# CombinedBoard_revA_1.net
KiCad netlist of a schematic drawn in EAGLE
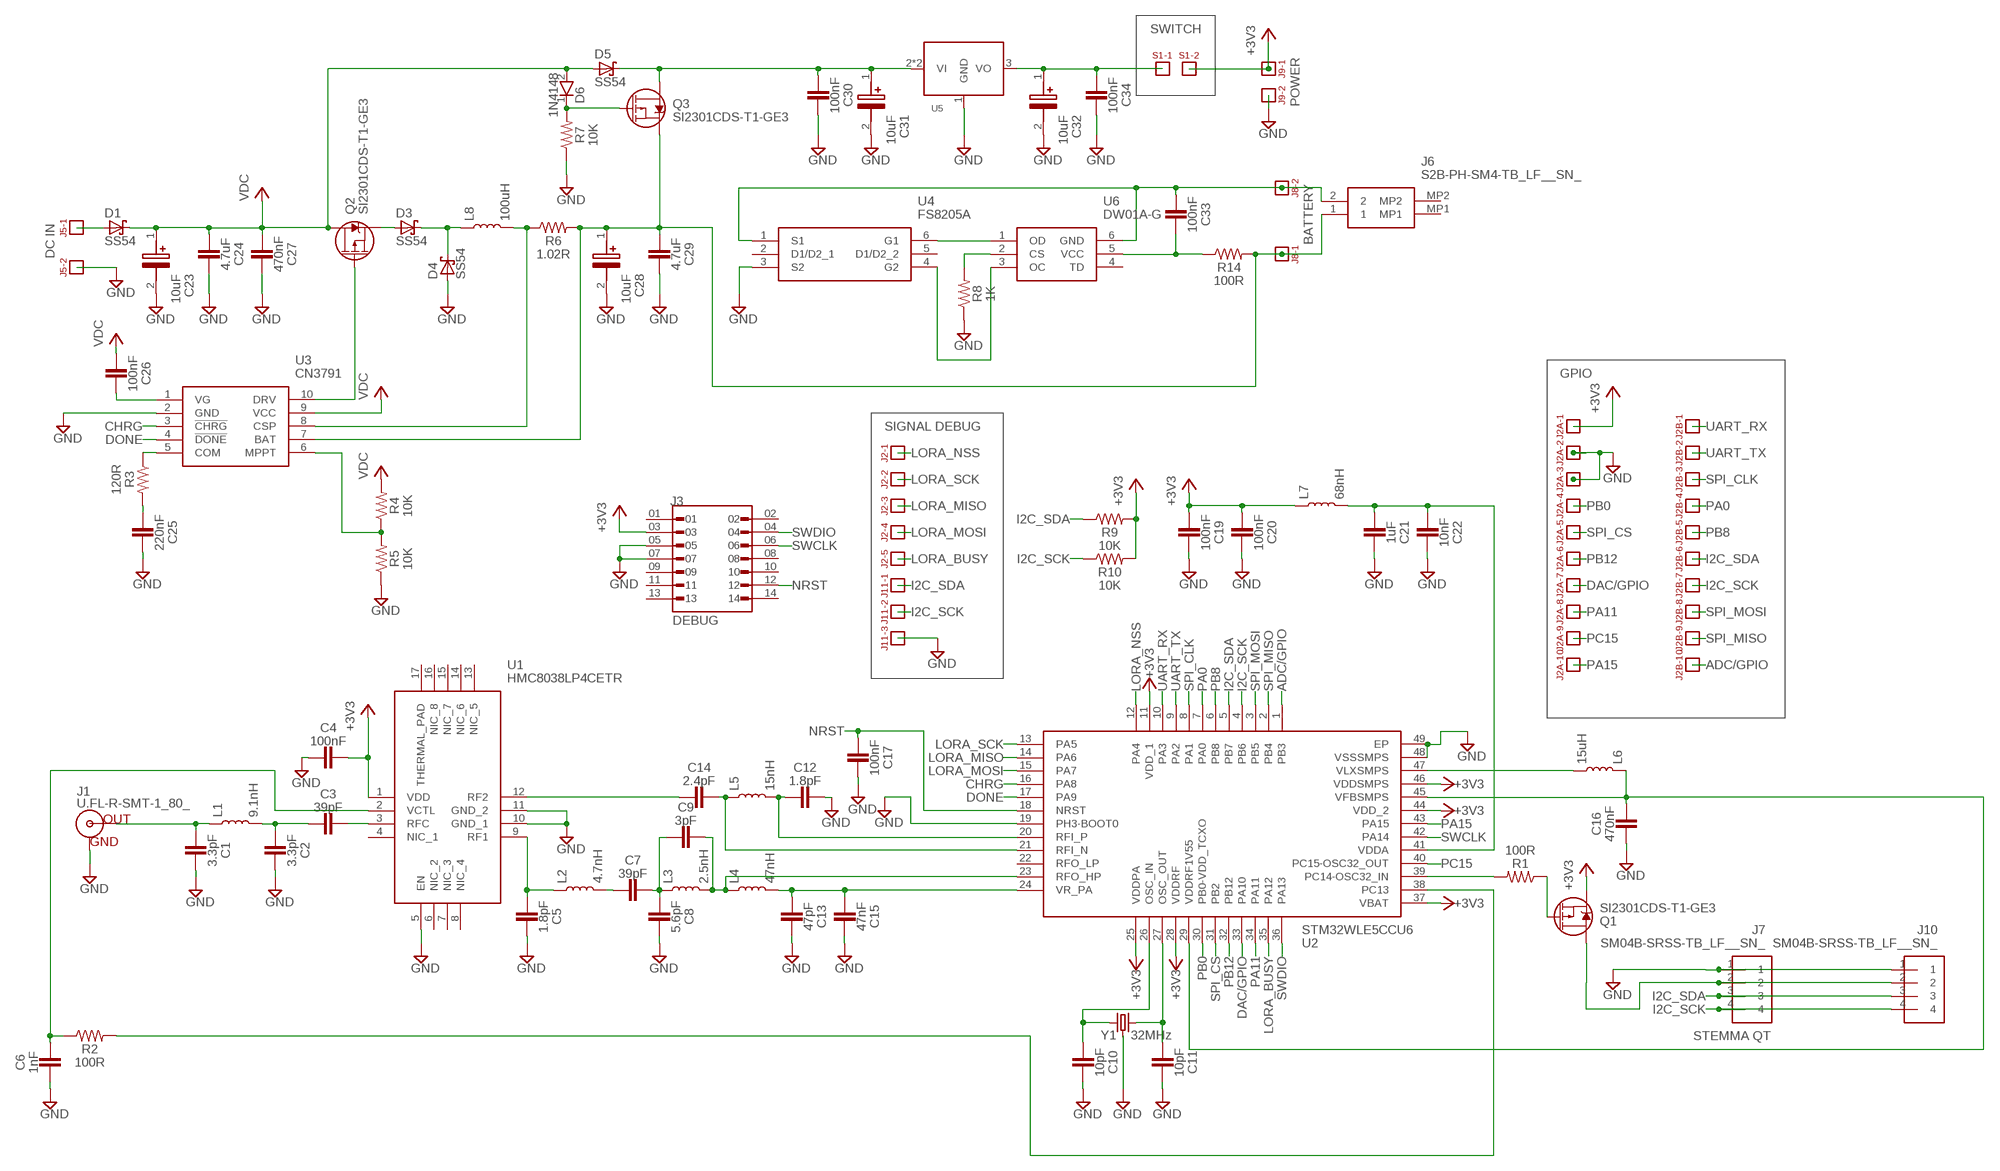
[diagram p0: schematic, sheet 1]

(export (version "E")
  (design (tool "Eeschema 10.0.6"))
  (components
    (comp (ref "C1")
      (value "3.3pF")
      (footprint "eagle-import:0402")
      (libsource (lib "eagle-import") (part "C_0402"))
    )
    (comp (ref "C2")
      (value "3.3pF")
      (footprint "eagle-import:0402")
      (libsource (lib "eagle-import") (part "C_0402"))
    )
    (comp (ref "C3")
      (value "39pF")
      (footprint "eagle-import:0402")
      (libsource (lib "eagle-import") (part "C_0402"))
    )
    (comp (ref "C4")
      (value "100nF")
      (footprint "eagle-import:0402")
      (libsource (lib "eagle-import") (part "C_0402"))
    )
    (comp (ref "C5")
      (value "1.8pF")
      (footprint "eagle-import:0402")
      (libsource (lib "eagle-import") (part "C_0402"))
    )
    (comp (ref "C6")
      (value "1nF")
      (footprint "eagle-import:0603")
      (libsource (lib "eagle-import") (part "C_0603"))
    )
    (comp (ref "C7")
      (value "39pF")
      (footprint "eagle-import:0402")
      (libsource (lib "eagle-import") (part "C_0402"))
    )
    (comp (ref "C8")
      (value "5.6pF")
      (footprint "eagle-import:0402")
      (libsource (lib "eagle-import") (part "C_0402"))
    )
    (comp (ref "C9")
      (value "3pF")
      (footprint "eagle-import:0603")
      (libsource (lib "eagle-import") (part "C_0603"))
    )
    (comp (ref "C10")
      (value "10pF")
      (footprint "eagle-import:0402")
      (libsource (lib "eagle-import") (part "C_0402"))
    )
    (comp (ref "C11")
      (value "10pF")
      (footprint "eagle-import:0402")
      (libsource (lib "eagle-import") (part "C_0402"))
    )
    (comp (ref "C12")
      (value "1.8pF")
      (footprint "eagle-import:0402")
      (libsource (lib "eagle-import") (part "C_0402"))
    )
    (comp (ref "C13")
      (value "47pF")
      (footprint "eagle-import:0603")
      (libsource (lib "eagle-import") (part "C_0603"))
    )
    (comp (ref "C14")
      (value "2.4pF")
      (footprint "eagle-import:0402")
      (libsource (lib "eagle-import") (part "C_0402"))
    )
    (comp (ref "C15")
      (value "47nF")
      (footprint "eagle-import:0603")
      (libsource (lib "eagle-import") (part "C_0603"))
    )
    (comp (ref "C16")
      (value "470nF")
      (footprint "eagle-import:0402")
      (libsource (lib "eagle-import") (part "C_0402"))
    )
    (comp (ref "C17")
      (value "100nF")
      (footprint "eagle-import:0402")
      (libsource (lib "eagle-import") (part "C_0402"))
    )
    (comp (ref "C19")
      (value "100nF")
      (footprint "eagle-import:0402")
      (libsource (lib "eagle-import") (part "C_0402"))
    )
    (comp (ref "C20")
      (value "100nF")
      (footprint "eagle-import:0402")
      (libsource (lib "eagle-import") (part "C_0402"))
    )
    (comp (ref "C21")
      (value "1uF")
      (footprint "eagle-import:0402")
      (libsource (lib "eagle-import") (part "C_0402"))
    )
    (comp (ref "C22")
      (value "10nF")
      (footprint "eagle-import:0402")
      (libsource (lib "eagle-import") (part "C_0402"))
    )
    (comp (ref "C23")
      (value "10uF")
      (footprint "eagle-import:4MM_SMD_ECAP")
      (libsource (lib "eagle-import") (part "4MM_SMD_ECAP"))
    )
    (comp (ref "C24")
      (value "4.7uF")
      (footprint "eagle-import:1206")
      (libsource (lib "eagle-import") (part "C_1206"))
    )
    (comp (ref "C25")
      (value "220nF")
      (footprint "eagle-import:0603")
      (libsource (lib "eagle-import") (part "C_0603"))
    )
    (comp (ref "C26")
      (value "100nF")
      (footprint "eagle-import:0402")
      (libsource (lib "eagle-import") (part "C_0402"))
    )
    (comp (ref "C27")
      (value "470nF")
      (footprint "eagle-import:0805")
      (libsource (lib "eagle-import") (part "C_0805"))
    )
    (comp (ref "C28")
      (value "10uF")
      (footprint "eagle-import:4MM_SMD_ECAP")
      (libsource (lib "eagle-import") (part "4MM_SMD_ECAP"))
    )
    (comp (ref "C29")
      (value "4.7uF")
      (footprint "eagle-import:1206")
      (libsource (lib "eagle-import") (part "C_1206"))
    )
    (comp (ref "C30")
      (value "100nF")
      (footprint "eagle-import:0402")
      (libsource (lib "eagle-import") (part "C_0402"))
    )
    (comp (ref "C31")
      (value "10uF")
      (footprint "eagle-import:4MM_SMD_ECAP")
      (libsource (lib "eagle-import") (part "4MM_SMD_ECAP"))
    )
    (comp (ref "C32")
      (value "10uF")
      (footprint "eagle-import:4MM_SMD_ECAP")
      (libsource (lib "eagle-import") (part "4MM_SMD_ECAP"))
    )
    (comp (ref "C33")
      (value "100nF")
      (footprint "eagle-import:0402")
      (libsource (lib "eagle-import") (part "C_0402"))
    )
    (comp (ref "C34")
      (value "100nF")
      (footprint "eagle-import:0402")
      (libsource (lib "eagle-import") (part "C_0402"))
    )
    (comp (ref "D1")
      (value "SS54")
      (footprint "eagle-import:SMA(DO-214AC)")
      (libsource (lib "eagle-import") (part "DIODE_SCHOTTKY_SMA"))
    )
    (comp (ref "D3")
      (value "SS54")
      (footprint "eagle-import:SMA(DO-214AC)")
      (libsource (lib "eagle-import") (part "DIODE_SCHOTTKY_SMA"))
    )
    (comp (ref "D4")
      (value "SS54")
      (footprint "eagle-import:SMA(DO-214AC)")
      (libsource (lib "eagle-import") (part "DIODE_SCHOTTKY_SMA"))
    )
    (comp (ref "D5")
      (value "SS54")
      (footprint "eagle-import:SMA(DO-214AC)")
      (libsource (lib "eagle-import") (part "DIODE_SCHOTTKY_SMA"))
    )
    (comp (ref "D6")
      (value "1N4148")
      (footprint "eagle-import:SOD3716X135N")
      (fields
        (field (name "ARROW_PART_NUMBER") "1N4148W-E3-08")
        (field (name "MOUSER_PART_NUMBER") "78-1N4148W-E3-08")
      )
      (libsource (lib "eagle-import") (part "1N4148W"))
    )
    (comp (ref "J1")
      (value "U.FL-R-SMT-1_80_")
      (footprint "eagle-import:UFLRSMT180")
      (fields
        (field (name "MANUFACTURER_PART_NUMBER") "U.FL-R-SMT-1(80)")
        (field (name "MOUSER_PART_NUMBER") "798-UFLRSMT180")
      )
      (libsource (lib "eagle-import") (part "U.FL-R-SMT-1_80_"))
    )
    (comp (ref "J2")
      (value "HEADER_5PIN")
      (footprint "eagle-import:HEADER_5PIN")
      (libsource (lib "eagle-import") (part "HEADER_5PIN"))
    )
    (comp (ref "J2A")
      (value "HEADER_10PIN")
      (footprint "eagle-import:HEADER_10PIN")
      (libsource (lib "eagle-import") (part "HEADER_10PIN"))
    )
    (comp (ref "J2B")
      (value "HEADER_10PIN")
      (footprint "eagle-import:HEADER_10PIN")
      (libsource (lib "eagle-import") (part "HEADER_10PIN"))
    )
    (comp (ref "J3")
      (value "DEBUG")
      (footprint "eagle-import:HEADER_DEBUG_SMD")
      (libsource (lib "eagle-import") (part "HEADER_DEBUG_SMD"))
    )
    (comp (ref "J5")
      (value "SOLAR")
      (footprint "eagle-import:HEADER_2PIN")
      (libsource (lib "eagle-import") (part "HEADER_2PIN"))
    )
    (comp (ref "J6")
      (value "S2B-PH-SM4-TB_LF__SN_")
      (footprint "eagle-import:S2BPHSM4TBLFSN")
      (fields (field (name "ARROW_PART_NUMBER") "S2B-PH-SM4-TB(LF)(SN)"))
      (libsource (lib "eagle-import") (part "S2B-PH-SM4-TB_LF__SN_"))
    )
    (comp (ref "J7")
      (value "SM04B-SRSS-TB_LF__SN_")
      (footprint "eagle-import:SM04B-SRSS-TB(LFSN)")
      (fields (field (name "ARROW_PART_NUMBER") "SM04B-SRSS-TB(LF)(SN)"))
      (libsource (lib "eagle-import") (part "SM04B-SRSS-TB_LF__SN_"))
    )
    (comp (ref "J8")
      (value "BATTERY")
      (footprint "eagle-import:HEADER_2PIN")
      (libsource (lib "eagle-import") (part "HEADER_2PIN"))
    )
    (comp (ref "J9")
      (value "POWER")
      (footprint "eagle-import:HEADER_2PIN")
      (libsource (lib "eagle-import") (part "HEADER_2PIN"))
    )
    (comp (ref "J10")
      (value "SM04B-SRSS-TB_LF__SN_")
      (footprint "eagle-import:SM04B-SRSS-TB(LFSN)")
      (fields (field (name "ARROW_PART_NUMBER") "SM04B-SRSS-TB(LF)(SN)"))
      (libsource (lib "eagle-import") (part "SM04B-SRSS-TB_LF__SN_"))
    )
    (comp (ref "J11")
      (value "HEADER_3PIN")
      (footprint "eagle-import:HEADER_3PIN")
      (libsource (lib "eagle-import") (part "HEADER_3PIN"))
    )
    (comp (ref "L1")
      (value "9.1nH")
      (footprint "eagle-import:0402")
      (libsource (lib "eagle-import") (part "L_0402"))
    )
    (comp (ref "L2")
      (value "4.7nH")
      (footprint "eagle-import:0402")
      (libsource (lib "eagle-import") (part "L_0402"))
    )
    (comp (ref "L3")
      (value "2.5nH")
      (footprint "eagle-import:0402")
      (libsource (lib "eagle-import") (part "L_0402"))
    )
    (comp (ref "L4")
      (value "47nH")
      (footprint "eagle-import:0603")
      (libsource (lib "eagle-import") (part "L_0603"))
    )
    (comp (ref "L5")
      (value "15nH")
      (footprint "eagle-import:0402")
      (libsource (lib "eagle-import") (part "L_0402"))
    )
    (comp (ref "L6")
      (value "15uH")
      (footprint "eagle-import:0805")
      (libsource (lib "eagle-import") (part "L_0805"))
    )
    (comp (ref "L7")
      (value "68nH")
      (footprint "eagle-import:0603")
      (libsource (lib "eagle-import") (part "L_0603"))
    )
    (comp (ref "L8")
      (value "100uH")
      (footprint "eagle-import:L_SMD,7X7.8MM")
      (libsource (lib "eagle-import") (part "L_SMD,7X7.8MM"))
    )
    (comp (ref "Q1")
      (value "SI2301CDS-T1-GE3")
      (footprint "eagle-import:SOT-23")
      (libsource (lib "eagle-import") (part "MOSFET_P_SOT23"))
    )
    (comp (ref "Q2")
      (value "SI2301CDS-T1-GE3")
      (footprint "eagle-import:SOT-23")
      (libsource (lib "eagle-import") (part "MOSFET_P_SOT23"))
    )
    (comp (ref "Q3")
      (value "SI2301CDS-T1-GE3")
      (footprint "eagle-import:SOT-23")
      (libsource (lib "eagle-import") (part "MOSFET_P_SOT23"))
    )
    (comp (ref "R1")
      (value "100R")
      (footprint "eagle-import:0402")
      (libsource (lib "eagle-import") (part "R_0402"))
    )
    (comp (ref "R2")
      (value "100R")
      (footprint "eagle-import:0402")
      (libsource (lib "eagle-import") (part "R_0402"))
    )
    (comp (ref "R3")
      (value "120R")
      (footprint "eagle-import:0805")
      (libsource (lib "eagle-import") (part "R_0805"))
    )
    (comp (ref "R4")
      (value "10K")
      (footprint "eagle-import:0402")
      (libsource (lib "eagle-import") (part "R_0402"))
    )
    (comp (ref "R5")
      (value "10K")
      (footprint "eagle-import:0402")
      (libsource (lib "eagle-import") (part "R_0402"))
    )
    (comp (ref "R6")
      (value "1.02R")
      (footprint "eagle-import:1206")
      (libsource (lib "eagle-import") (part "R_1206"))
    )
    (comp (ref "R7")
      (value "10K")
      (footprint "eagle-import:0402")
      (libsource (lib "eagle-import") (part "R_0402"))
    )
    (comp (ref "R8")
      (value "1K")
      (footprint "eagle-import:0402")
      (libsource (lib "eagle-import") (part "R_0402"))
    )
    (comp (ref "R9")
      (value "10K")
      (footprint "eagle-import:0402")
      (libsource (lib "eagle-import") (part "R_0402"))
    )
    (comp (ref "R10")
      (value "10K")
      (footprint "eagle-import:0402")
      (libsource (lib "eagle-import") (part "R_0402"))
    )
    (comp (ref "R14")
      (value "100R")
      (footprint "eagle-import:0402")
      (libsource (lib "eagle-import") (part "R_0402"))
    )
    (comp (ref "S1")
      (value "HEADER_2PIN")
      (footprint "eagle-import:HEADER_2PIN")
      (libsource (lib "eagle-import") (part "HEADER_2PIN"))
    )
    (comp (ref "U1")
      (value "HMC8038LP4CETR")
      (footprint "eagle-import:QFN65P400X400X90-17N")
      (fields (field (name "MOUSER_PART_NUMBER") "584-HMC8038LP4CETR"))
      (libsource (lib "eagle-import") (part "HMC8038LP4CETR"))
    )
    (comp (ref "U2")
      (value "STM32WLE5CCU6")
      (footprint "eagle-import:QFN50P700X700X60-49N")
      (fields (field (name "MOUSER_PART_NUMBER") "511-STM32WLE5CCU6"))
      (libsource (lib "eagle-import") (part "STM32WLE5CCU6"))
    )
    (comp (ref "U3")
      (value "CN3791")
      (footprint "eagle-import:SOP100P600X175-10N")
      (libsource (lib "eagle-import") (part "CN3791"))
    )
    (comp (ref "U4")
      (value "FS8205A")
      (footprint "eagle-import:SOT95P280X125-6N")
      (libsource (lib "eagle-import") (part "FS8205A"))
    )
    (comp (ref "U5")
      (value "LDO_SOT89")
      (footprint "eagle-import:SOT-89-3")
      (libsource (lib "eagle-import") (part "LDO_SOT89"))
    )
    (comp (ref "U6")
      (value "DW01A-G")
      (footprint "eagle-import:SOT95P280X135-6N")
      (libsource (lib "eagle-import") (part "DW01A-G"))
    )
    (comp (ref "Y1")
      (value "32MHz")
      (footprint "eagle-import:SMD2016-4P")
      (libsource (lib "eagle-import") (part "XTAL_SMD2016-4P"))
    )
  )
  (nets
    (net (code "1") (name "+3V3") (class "Default")
      (node (ref "C19") (pin "1") (pinfunction "1_1") (pintype "passive"))
      (node (ref "C20") (pin "1") (pinfunction "1_1") (pintype "passive"))
      (node (ref "C4") (pin "2") (pinfunction "2_2") (pintype "passive"))
      (node (ref "J2A") (pin "P$1") (pinfunction "P$1_P$1") (pintype "bidirectional"))
      (node (ref "J3") (pin "03") (pinfunction "03_03") (pintype "passive"))
      (node (ref "J9") (pin "P$1") (pinfunction "P$1_P$1") (pintype "bidirectional"))
      (node (ref "L7") (pin "1") (pinfunction "1_1") (pintype "passive"))
      (node (ref "Q1") (pin "3") (pinfunction "S_3") (pintype "bidirectional"))
      (node (ref "R10") (pin "2") (pinfunction "2_2") (pintype "passive"))
      (node (ref "R9") (pin "2") (pinfunction "2_2") (pintype "passive"))
      (node (ref "S1") (pin "P$2") (pinfunction "P$1_P$2") (pintype "bidirectional"))
      (node (ref "U1") (pin "1") (pinfunction "VDD_1") (pintype "bidirectional"))
      (node (ref "U2") (pin "11") (pinfunction "VDD_1_11") (pintype "bidirectional"))
      (node (ref "U2") (pin "25") (pinfunction "VDDPA_25") (pintype "bidirectional"))
      (node (ref "U2") (pin "28") (pinfunction "VDDRF_28") (pintype "bidirectional"))
      (node (ref "U2") (pin "37") (pinfunction "VBAT_37") (pintype "bidirectional"))
      (node (ref "U2") (pin "44") (pinfunction "VDD_2_44") (pintype "bidirectional"))
      (node (ref "U2") (pin "46") (pinfunction "VDDSMPS_46") (pintype "bidirectional"))
    )
    (net (code "2") (name "/ADC{slash}GPIO") (class "Default")
      (node (ref "J2B") (pin "P$10") (pinfunction "P$1_P$10") (pintype "bidirectional"))
      (node (ref "U2") (pin "1") (pinfunction "PB3_1") (pintype "bidirectional"))
    )
    (net (code "3") (name "/CHRG") (class "Default")
      (node (ref "U2") (pin "16") (pinfunction "PA8_16") (pintype "bidirectional"))
      (node (ref "U3") (pin "3") (pinfunction "~{CHRG}_3") (pintype "bidirectional"))
    )
    (net (code "4") (name "/DAC{slash}GPIO") (class "Default")
      (node (ref "J2A") (pin "P$7") (pinfunction "P$1_P$7") (pintype "bidirectional"))
      (node (ref "U2") (pin "33") (pinfunction "PA10_33") (pintype "bidirectional"))
    )
    (net (code "5") (name "/DONE") (class "Default")
      (node (ref "U2") (pin "17") (pinfunction "PA9_17") (pintype "bidirectional"))
      (node (ref "U3") (pin "4") (pinfunction "~{DONE}_4") (pintype "bidirectional"))
    )
    (net (code "6") (name "/I2C_SCK") (class "Default")
      (node (ref "J10") (pin "4") (pinfunction "4_4") (pintype "bidirectional"))
      (node (ref "J11") (pin "P$2") (pinfunction "P$1_P$2") (pintype "bidirectional"))
      (node (ref "J2B") (pin "P$7") (pinfunction "P$1_P$7") (pintype "bidirectional"))
      (node (ref "J7") (pin "4") (pinfunction "4_4") (pintype "bidirectional"))
      (node (ref "R10") (pin "1") (pinfunction "1_1") (pintype "passive"))
      (node (ref "U2") (pin "4") (pinfunction "PB6_4") (pintype "bidirectional"))
    )
    (net (code "7") (name "/I2C_SDA") (class "Default")
      (node (ref "J10") (pin "3") (pinfunction "3_3") (pintype "bidirectional"))
      (node (ref "J11") (pin "P$1") (pinfunction "P$1_P$1") (pintype "bidirectional"))
      (node (ref "J2B") (pin "P$6") (pinfunction "P$1_P$6") (pintype "bidirectional"))
      (node (ref "J7") (pin "3") (pinfunction "3_3") (pintype "bidirectional"))
      (node (ref "R9") (pin "1") (pinfunction "1_1") (pintype "passive"))
      (node (ref "U2") (pin "5") (pinfunction "PB7_5") (pintype "bidirectional"))
    )
    (net (code "8") (name "/LORA_BUSY") (class "Default")
      (node (ref "J2") (pin "P$5") (pinfunction "P$1_P$5") (pintype "bidirectional"))
      (node (ref "U2") (pin "35") (pinfunction "PA12_35") (pintype "bidirectional"))
    )
    (net (code "9") (name "/LORA_MISO") (class "Default")
      (node (ref "J2") (pin "P$3") (pinfunction "P$1_P$3") (pintype "bidirectional"))
      (node (ref "U2") (pin "14") (pinfunction "PA6_14") (pintype "bidirectional"))
    )
    (net (code "10") (name "/LORA_MOSI") (class "Default")
      (node (ref "J2") (pin "P$4") (pinfunction "P$1_P$4") (pintype "bidirectional"))
      (node (ref "U2") (pin "15") (pinfunction "PA7_15") (pintype "bidirectional"))
    )
    (net (code "11") (name "/LORA_NSS") (class "Default")
      (node (ref "J2") (pin "P$1") (pinfunction "P$1_P$1") (pintype "bidirectional"))
      (node (ref "U2") (pin "12") (pinfunction "PA4_12") (pintype "bidirectional"))
    )
    (net (code "12") (name "/LORA_SCK") (class "Default")
      (node (ref "J2") (pin "P$2") (pinfunction "P$1_P$2") (pintype "bidirectional"))
      (node (ref "U2") (pin "13") (pinfunction "PA5_13") (pintype "bidirectional"))
    )
    (net (code "13") (name "/NRST") (class "Default")
      (node (ref "C17") (pin "1") (pinfunction "1_1") (pintype "passive"))
      (node (ref "J3") (pin "12") (pinfunction "12_12") (pintype "passive"))
      (node (ref "U2") (pin "18") (pinfunction "NRST_18") (pintype "bidirectional"))
    )
    (net (code "14") (name "/PA0") (class "Default")
      (node (ref "J2B") (pin "P$4") (pinfunction "P$1_P$4") (pintype "bidirectional"))
      (node (ref "U2") (pin "7") (pinfunction "PA0_7") (pintype "bidirectional"))
    )
    (net (code "15") (name "/PA11") (class "Default")
      (node (ref "J2A") (pin "P$8") (pinfunction "P$1_P$8") (pintype "bidirectional"))
      (node (ref "U2") (pin "34") (pinfunction "PA11_34") (pintype "bidirectional"))
    )
    (net (code "16") (name "/PA15") (class "Default")
      (node (ref "J2A") (pin "P$10") (pinfunction "P$1_P$10") (pintype "bidirectional"))
      (node (ref "U2") (pin "43") (pinfunction "PA15_43") (pintype "bidirectional"))
    )
    (net (code "17") (name "/PB0") (class "Default")
      (node (ref "J2A") (pin "P$4") (pinfunction "P$1_P$4") (pintype "bidirectional"))
      (node (ref "U2") (pin "30") (pinfunction "PB0-VDD_TCXO_30") (pintype "bidirectional"))
    )
    (net (code "18") (name "/PB8") (class "Default")
      (node (ref "J2B") (pin "P$5") (pinfunction "P$1_P$5") (pintype "bidirectional"))
      (node (ref "U2") (pin "6") (pinfunction "PB8_6") (pintype "bidirectional"))
    )
    (net (code "19") (name "/PB12") (class "Default")
      (node (ref "J2A") (pin "P$6") (pinfunction "P$1_P$6") (pintype "bidirectional"))
      (node (ref "U2") (pin "32") (pinfunction "PB12_32") (pintype "bidirectional"))
    )
    (net (code "20") (name "/PC15") (class "Default")
      (node (ref "J2A") (pin "P$9") (pinfunction "P$1_P$9") (pintype "bidirectional"))
      (node (ref "U2") (pin "40") (pinfunction "PC15-OSC32_OUT_40") (pintype "bidirectional"))
    )
    (net (code "21") (name "/SPI_CLK") (class "Default")
      (node (ref "J2B") (pin "P$3") (pinfunction "P$1_P$3") (pintype "bidirectional"))
      (node (ref "U2") (pin "8") (pinfunction "PA1_8") (pintype "bidirectional"))
    )
    (net (code "22") (name "/SPI_CS") (class "Default")
      (node (ref "J2A") (pin "P$5") (pinfunction "P$1_P$5") (pintype "bidirectional"))
      (node (ref "U2") (pin "31") (pinfunction "PB2_31") (pintype "bidirectional"))
    )
    (net (code "23") (name "/SPI_MISO") (class "Default")
      (node (ref "J2B") (pin "P$9") (pinfunction "P$1_P$9") (pintype "bidirectional"))
      (node (ref "U2") (pin "2") (pinfunction "PB4_2") (pintype "bidirectional"))
    )
    (net (code "24") (name "/SPI_MOSI") (class "Default")
      (node (ref "J2B") (pin "P$8") (pinfunction "P$1_P$8") (pintype "bidirectional"))
      (node (ref "U2") (pin "3") (pinfunction "PB5_3") (pintype "bidirectional"))
    )
    (net (code "25") (name "/SWCLK") (class "Default")
      (node (ref "J3") (pin "06") (pinfunction "06_06") (pintype "passive"))
      (node (ref "U2") (pin "42") (pinfunction "PA14_42") (pintype "bidirectional"))
    )
    (net (code "26") (name "/SWDIO") (class "Default")
      (node (ref "J3") (pin "04") (pinfunction "04_04") (pintype "passive"))
      (node (ref "U2") (pin "36") (pinfunction "PA13_36") (pintype "bidirectional"))
    )
    (net (code "27") (name "/UART_RX") (class "Default")
      (node (ref "J2B") (pin "P$1") (pinfunction "P$1_P$1") (pintype "bidirectional"))
      (node (ref "U2") (pin "10") (pinfunction "PA3_10") (pintype "bidirectional"))
    )
    (net (code "28") (name "/UART_TX") (class "Default")
      (node (ref "J2B") (pin "P$2") (pinfunction "P$1_P$2") (pintype "bidirectional"))
      (node (ref "U2") (pin "9") (pinfunction "PA2_9") (pintype "bidirectional"))
    )
    (net (code "29") (name "GND") (class "Default")
      (node (ref "C1") (pin "2") (pinfunction "2_2") (pintype "passive"))
      (node (ref "C10") (pin "2") (pinfunction "2_2") (pintype "passive"))
      (node (ref "C11") (pin "2") (pinfunction "2_2") (pintype "passive"))
      (node (ref "C12") (pin "2") (pinfunction "2_2") (pintype "passive"))
      (node (ref "C13") (pin "2") (pinfunction "2_2") (pintype "passive"))
      (node (ref "C15") (pin "2") (pinfunction "2_2") (pintype "passive"))
      (node (ref "C16") (pin "1") (pinfunction "1_1") (pintype "passive"))
      (node (ref "C17") (pin "2") (pinfunction "2_2") (pintype "passive"))
      (node (ref "C19") (pin "2") (pinfunction "2_2") (pintype "passive"))
      (node (ref "C2") (pin "2") (pinfunction "2_2") (pintype "passive"))
      (node (ref "C20") (pin "2") (pinfunction "2_2") (pintype "passive"))
      (node (ref "C21") (pin "2") (pinfunction "2_2") (pintype "passive"))
      (node (ref "C22") (pin "2") (pinfunction "2_2") (pintype "passive"))
      (node (ref "C23") (pin "2") (pinfunction "-_2") (pintype "bidirectional"))
      (node (ref "C24") (pin "2") (pinfunction "2_2") (pintype "passive"))
      (node (ref "C25") (pin "2") (pinfunction "2_2") (pintype "passive"))
      (node (ref "C27") (pin "2") (pinfunction "2_2") (pintype "passive"))
      (node (ref "C28") (pin "2") (pinfunction "-_2") (pintype "bidirectional"))
      (node (ref "C29") (pin "2") (pinfunction "2_2") (pintype "passive"))
      (node (ref "C30") (pin "2") (pinfunction "2_2") (pintype "passive"))
      (node (ref "C31") (pin "2") (pinfunction "-_2") (pintype "bidirectional"))
      (node (ref "C32") (pin "2") (pinfunction "-_2") (pintype "bidirectional"))
      (node (ref "C34") (pin "2") (pinfunction "2_2") (pintype "passive"))
      (node (ref "C4") (pin "1") (pinfunction "1_1") (pintype "passive"))
      (node (ref "C5") (pin "2") (pinfunction "2_2") (pintype "passive"))
      (node (ref "C6") (pin "1") (pinfunction "1_1") (pintype "passive"))
      (node (ref "C8") (pin "2") (pinfunction "2_2") (pintype "passive"))
      (node (ref "D4") (pin "2") (pinfunction "A_2") (pintype "passive"))
      (node (ref "J1") (pin "2") (pinfunction "GND_2") (pintype "bidirectional"))
      (node (ref "J1") (pin "3") (pinfunction "GND_3") (pintype "bidirectional"))
      (node (ref "J10") (pin "1") (pinfunction "1_1") (pintype "bidirectional"))
      (node (ref "J11") (pin "P$3") (pinfunction "P$1_P$3") (pintype "bidirectional"))
      (node (ref "J2A") (pin "P$2") (pinfunction "P$1_P$2") (pintype "bidirectional"))
      (node (ref "J2A") (pin "P$3") (pinfunction "P$1_P$3") (pintype "bidirectional"))
      (node (ref "J3") (pin "05") (pinfunction "05_05") (pintype "passive"))
      (node (ref "J3") (pin "07") (pinfunction "07_07") (pintype "passive"))
      (node (ref "J5") (pin "P$2") (pinfunction "P$1_P$2") (pintype "bidirectional"))
      (node (ref "J7") (pin "1") (pinfunction "1_1") (pintype "bidirectional"))
      (node (ref "J9") (pin "P$2") (pinfunction "P$1_P$2") (pintype "bidirectional"))
      (node (ref "R5") (pin "1") (pinfunction "1_1") (pintype "passive"))
      (node (ref "R7") (pin "1") (pinfunction "1_1") (pintype "passive"))
      (node (ref "R8") (pin "1") (pinfunction "1_1") (pintype "passive"))
      (node (ref "U1") (pin "10") (pinfunction "GND_1_10") (pintype "bidirectional"))
      (node (ref "U1") (pin "11") (pinfunction "GND_2_11") (pintype "bidirectional"))
      (node (ref "U1") (pin "5") (pinfunction "EN_5") (pintype "bidirectional"))
      (node (ref "U2") (pin "19") (pinfunction "PH3-BOOT0_19") (pintype "bidirectional"))
      (node (ref "U2") (pin "48") (pinfunction "VSSSMPS_48") (pintype "bidirectional"))
      (node (ref "U2") (pin "49") (pinfunction "EP_49") (pintype "bidirectional"))
      (node (ref "U3") (pin "2") (pinfunction "GND_2") (pintype "bidirectional"))
      (node (ref "U4") (pin "3") (pinfunction "S2_3") (pintype "bidirectional"))
      (node (ref "U5") (pin "1") (pinfunction "GND_1") (pintype "bidirectional"))
      (node (ref "Y1") (pin "2") (pinfunction "3_2") (pintype "passive"))
      (node (ref "Y1") (pin "4") (pinfunction "3_4") (pintype "passive"))
    )
    (net (code "30") (name "Net-(C2-Pad1)") (class "Default")
      (node (ref "C2") (pin "1") (pinfunction "1_1") (pintype "passive"))
      (node (ref "C3") (pin "1") (pinfunction "1_1") (pintype "passive"))
      (node (ref "L1") (pin "2") (pinfunction "2_2") (pintype "passive"))
    )
    (net (code "31") (name "Net-(C7-Pad1)") (class "Default")
      (node (ref "C7") (pin "1") (pinfunction "1_1") (pintype "passive"))
      (node (ref "L2") (pin "2") (pinfunction "2_2") (pintype "passive"))
    )
    (net (code "32") (name "Net-(C7-Pad2)") (class "Default")
      (node (ref "C7") (pin "2") (pinfunction "2_2") (pintype "passive"))
      (node (ref "C8") (pin "1") (pinfunction "1_1") (pintype "passive"))
      (node (ref "C9") (pin "1") (pinfunction "1_1") (pintype "passive"))
      (node (ref "L3") (pin "1") (pinfunction "1_1") (pintype "passive"))
    )
    (net (code "33") (name "Net-(C25-Pad1)") (class "Default")
      (node (ref "C25") (pin "1") (pinfunction "1_1") (pintype "passive"))
      (node (ref "R3") (pin "2") (pinfunction "2_2") (pintype "passive"))
    )
    (net (code "34") (name "Net-(C28-+)") (class "Default")
      (node (ref "C28") (pin "1") (pinfunction "+_1") (pintype "bidirectional"))
      (node (ref "C29") (pin "1") (pinfunction "1_1") (pintype "passive"))
      (node (ref "J6") (pin "1") (pinfunction "1_1") (pintype "bidirectional"))
      (node (ref "J8") (pin "P$1") (pinfunction "P$1_P$1") (pintype "bidirectional"))
      (node (ref "Q3") (pin "3") (pinfunction "S_3") (pintype "bidirectional"))
      (node (ref "R14") (pin "2") (pinfunction "2_2") (pintype "passive"))
      (node (ref "R6") (pin "2") (pinfunction "2_2") (pintype "passive"))
      (node (ref "U3") (pin "7") (pinfunction "BAT_7") (pintype "bidirectional"))
    )
    (net (code "35") (name "Net-(C31-+)") (class "Default")
      (node (ref "C30") (pin "1") (pinfunction "1_1") (pintype "passive"))
      (node (ref "C31") (pin "1") (pinfunction "+_1") (pintype "bidirectional"))
      (node (ref "D5") (pin "1") (pinfunction "C_1") (pintype "passive"))
      (node (ref "Q3") (pin "2") (pinfunction "D_2") (pintype "bidirectional"))
      (node (ref "U5") (pin "2") (pinfunction "VI_2") (pintype "bidirectional"))
      (node (ref "U5") (pin "4") (pinfunction "VI_4") (pintype "bidirectional"))
    )
    (net (code "36") (name "Net-(C32-+)") (class "Default")
      (node (ref "C32") (pin "1") (pinfunction "+_1") (pintype "bidirectional"))
      (node (ref "C34") (pin "1") (pinfunction "1_1") (pintype "passive"))
      (node (ref "S1") (pin "P$1") (pinfunction "P$1_P$1") (pintype "bidirectional"))
      (node (ref "U5") (pin "3") (pinfunction "VO_3") (pintype "bidirectional"))
    )
    (net (code "37") (name "Net-(D1-A)") (class "Default")
      (node (ref "D1") (pin "2") (pinfunction "A_2") (pintype "passive"))
      (node (ref "J5") (pin "P$1") (pinfunction "P$1_P$1") (pintype "bidirectional"))
    )
    (net (code "38") (name "Net-(D3-A)") (class "Default")
      (node (ref "D3") (pin "2") (pinfunction "A_2") (pintype "passive"))
      (node (ref "Q2") (pin "3") (pinfunction "S_3") (pintype "bidirectional"))
    )
    (net (code "39") (name "Net-(D3-C)") (class "Default")
      (node (ref "D3") (pin "1") (pinfunction "C_1") (pintype "passive"))
      (node (ref "D4") (pin "1") (pinfunction "C_1") (pintype "passive"))
      (node (ref "L8") (pin "P$1") (pinfunction "1_P$1") (pintype "passive"))
    )
    (net (code "40") (name "Net-(D6-K)") (class "Default")
      (node (ref "D6") (pin "1") (pinfunction "K_1") (pintype "bidirectional"))
      (node (ref "Q3") (pin "1") (pinfunction "G_1") (pintype "bidirectional"))
      (node (ref "R7") (pin "2") (pinfunction "2_2") (pintype "passive"))
    )
    (net (code "41") (name "Net-(J1-OUT)") (class "Default")
      (node (ref "C1") (pin "1") (pinfunction "1_1") (pintype "passive"))
      (node (ref "J1") (pin "1") (pinfunction "OUT_1") (pintype "bidirectional"))
      (node (ref "L1") (pin "1") (pinfunction "1_1") (pintype "passive"))
    )
    (net (code "42") (name "Net-(J8B-P$1)") (class "Default")
      (node (ref "C33") (pin "1") (pinfunction "1_1") (pintype "passive"))
      (node (ref "J6") (pin "2") (pinfunction "2_2") (pintype "bidirectional"))
      (node (ref "J8") (pin "P$2") (pinfunction "P$1_P$2") (pintype "bidirectional"))
      (node (ref "U4") (pin "1") (pinfunction "S1_1") (pintype "bidirectional"))
      (node (ref "U6") (pin "6") (pinfunction "GND_6") (pintype "bidirectional"))
    )
    (net (code "43") (name "Net-(L8-2)") (class "Default")
      (node (ref "L8") (pin "P$2") (pinfunction "2_P$2") (pintype "passive"))
      (node (ref "R6") (pin "1") (pinfunction "1_1") (pintype "passive"))
      (node (ref "U3") (pin "8") (pinfunction "CSP_8") (pintype "bidirectional"))
    )
    (net (code "44") (name "Net-(Q1-D)") (class "Default")
      (node (ref "J10") (pin "2") (pinfunction "2_2") (pintype "bidirectional"))
      (node (ref "J7") (pin "2") (pinfunction "2_2") (pintype "bidirectional"))
      (node (ref "Q1") (pin "2") (pinfunction "D_2") (pintype "bidirectional"))
    )
    (net (code "45") (name "Net-(Q1-G)") (class "Default")
      (node (ref "Q1") (pin "1") (pinfunction "G_1") (pintype "bidirectional"))
      (node (ref "R1") (pin "1") (pinfunction "1_1") (pintype "passive"))
    )
    (net (code "46") (name "Net-(Q2-G)") (class "Default")
      (node (ref "Q2") (pin "1") (pinfunction "G_1") (pintype "bidirectional"))
      (node (ref "U3") (pin "10") (pinfunction "DRV_10") (pintype "bidirectional"))
    )
    (net (code "47") (name "Net-(U1-RF1)") (class "Default")
      (node (ref "C5") (pin "1") (pinfunction "1_1") (pintype "passive"))
      (node (ref "L2") (pin "1") (pinfunction "1_1") (pintype "passive"))
      (node (ref "U1") (pin "9") (pinfunction "RF1_9") (pintype "bidirectional"))
    )
    (net (code "48") (name "Net-(U1-RF2)") (class "Default")
      (node (ref "C14") (pin "1") (pinfunction "1_1") (pintype "passive"))
      (node (ref "U1") (pin "12") (pinfunction "RF2_12") (pintype "bidirectional"))
    )
    (net (code "49") (name "Net-(U1-RFC)") (class "Default")
      (node (ref "C3") (pin "2") (pinfunction "2_2") (pintype "passive"))
      (node (ref "U1") (pin "3") (pinfunction "RFC_3") (pintype "bidirectional"))
    )
    (net (code "50") (name "Net-(U1-VCTL)") (class "Default")
      (node (ref "C6") (pin "2") (pinfunction "2_2") (pintype "passive"))
      (node (ref "R2") (pin "1") (pinfunction "1_1") (pintype "passive"))
      (node (ref "U1") (pin "2") (pinfunction "VCTL_2") (pintype "bidirectional"))
    )
    (net (code "51") (name "Net-(U2-OSC_IN)") (class "Default")
      (node (ref "C10") (pin "1") (pinfunction "1_1") (pintype "passive"))
      (node (ref "U2") (pin "26") (pinfunction "OSC_IN_26") (pintype "bidirectional"))
      (node (ref "Y1") (pin "1") (pinfunction "1_1") (pintype "passive"))
    )
    (net (code "52") (name "Net-(U2-OSC_OUT)") (class "Default")
      (node (ref "C11") (pin "1") (pinfunction "1_1") (pintype "passive"))
      (node (ref "U2") (pin "27") (pinfunction "OSC_OUT_27") (pintype "bidirectional"))
      (node (ref "Y1") (pin "3") (pinfunction "2_3") (pintype "passive"))
    )
    (net (code "53") (name "Net-(U2-PC13)") (class "Default")
      (node (ref "R2") (pin "2") (pinfunction "2_2") (pintype "passive"))
      (node (ref "U2") (pin "38") (pinfunction "PC13_38") (pintype "bidirectional"))
    )
    (net (code "54") (name "Net-(U2-PC14-OSC32_IN)") (class "Default")
      (node (ref "R1") (pin "2") (pinfunction "2_2") (pintype "passive"))
      (node (ref "U2") (pin "39") (pinfunction "PC14-OSC32_IN_39") (pintype "bidirectional"))
    )
    (net (code "55") (name "Net-(U2-RFI_N)") (class "Default")
      (node (ref "C14") (pin "2") (pinfunction "2_2") (pintype "passive"))
      (node (ref "L5") (pin "1") (pinfunction "1_1") (pintype "passive"))
      (node (ref "U2") (pin "21") (pinfunction "RFI_N_21") (pintype "bidirectional"))
    )
    (net (code "56") (name "Net-(U2-RFI_P)") (class "Default")
      (node (ref "C12") (pin "1") (pinfunction "1_1") (pintype "passive"))
      (node (ref "L5") (pin "2") (pinfunction "2_2") (pintype "passive"))
      (node (ref "U2") (pin "20") (pinfunction "RFI_P_20") (pintype "bidirectional"))
    )
    (net (code "57") (name "Net-(U2-RFO_HP)") (class "Default")
      (node (ref "C9") (pin "2") (pinfunction "2_2") (pintype "passive"))
      (node (ref "L3") (pin "2") (pinfunction "2_2") (pintype "passive"))
      (node (ref "L4") (pin "1") (pinfunction "1_1") (pintype "passive"))
      (node (ref "U2") (pin "23") (pinfunction "RFO_HP_23") (pintype "bidirectional"))
    )
    (net (code "58") (name "Net-(U2-VDDA)") (class "Default")
      (node (ref "C21") (pin "1") (pinfunction "1_1") (pintype "passive"))
      (node (ref "C22") (pin "1") (pinfunction "1_1") (pintype "passive"))
      (node (ref "L7") (pin "2") (pinfunction "2_2") (pintype "passive"))
      (node (ref "U2") (pin "41") (pinfunction "VDDA_41") (pintype "bidirectional"))
    )
    (net (code "59") (name "Net-(U2-VDDRF1V55)") (class "Default")
      (node (ref "C16") (pin "2") (pinfunction "2_2") (pintype "passive"))
      (node (ref "L6") (pin "1") (pinfunction "1_1") (pintype "passive"))
      (node (ref "U2") (pin "29") (pinfunction "VDDRF1V55_29") (pintype "bidirectional"))
      (node (ref "U2") (pin "45") (pinfunction "VFBSMPS_45") (pintype "bidirectional"))
    )
    (net (code "60") (name "Net-(U2-VLXSMPS)") (class "Default")
      (node (ref "L6") (pin "2") (pinfunction "2_2") (pintype "passive"))
      (node (ref "U2") (pin "47") (pinfunction "VLXSMPS_47") (pintype "bidirectional"))
    )
    (net (code "61") (name "Net-(U2-VR_PA)") (class "Default")
      (node (ref "C13") (pin "1") (pinfunction "1_1") (pintype "passive"))
      (node (ref "C15") (pin "1") (pinfunction "1_1") (pintype "passive"))
      (node (ref "L4") (pin "2") (pinfunction "2_2") (pintype "passive"))
      (node (ref "U2") (pin "24") (pinfunction "VR_PA_24") (pintype "bidirectional"))
    )
    (net (code "62") (name "Net-(U3-COM)") (class "Default")
      (node (ref "R3") (pin "1") (pinfunction "1_1") (pintype "passive"))
      (node (ref "U3") (pin "5") (pinfunction "COM_5") (pintype "bidirectional"))
    )
    (net (code "63") (name "Net-(U3-MPPT)") (class "Default")
      (node (ref "R4") (pin "1") (pinfunction "1_1") (pintype "passive"))
      (node (ref "R5") (pin "2") (pinfunction "2_2") (pintype "passive"))
      (node (ref "U3") (pin "6") (pinfunction "MPPT_6") (pintype "bidirectional"))
    )
    (net (code "64") (name "Net-(U3-VG)") (class "Default")
      (node (ref "C26") (pin "2") (pinfunction "2_2") (pintype "passive"))
      (node (ref "U3") (pin "1") (pinfunction "VG_1") (pintype "bidirectional"))
    )
    (net (code "65") (name "Net-(U4-G1)") (class "Default")
      (node (ref "U4") (pin "6") (pinfunction "G1_6") (pintype "bidirectional"))
      (node (ref "U6") (pin "1") (pinfunction "OD_1") (pintype "bidirectional"))
    )
    (net (code "66") (name "Net-(U4-G2)") (class "Default")
      (node (ref "U4") (pin "4") (pinfunction "G2_4") (pintype "bidirectional"))
      (node (ref "U6") (pin "3") (pinfunction "OC_3") (pintype "bidirectional"))
    )
    (net (code "67") (name "Net-(U6-CS)") (class "Default")
      (node (ref "R8") (pin "2") (pinfunction "2_2") (pintype "passive"))
      (node (ref "U6") (pin "2") (pinfunction "CS_2") (pintype "bidirectional"))
    )
    (net (code "68") (name "Net-(U6-VCC)") (class "Default")
      (node (ref "C33") (pin "2") (pinfunction "2_2") (pintype "passive"))
      (node (ref "R14") (pin "1") (pinfunction "1_1") (pintype "passive"))
      (node (ref "U6") (pin "5") (pinfunction "VCC_5") (pintype "bidirectional"))
    )
    (net (code "69") (name "VDC") (class "Default")
      (node (ref "C23") (pin "1") (pinfunction "+_1") (pintype "bidirectional"))
      (node (ref "C24") (pin "1") (pinfunction "1_1") (pintype "passive"))
      (node (ref "C26") (pin "1") (pinfunction "1_1") (pintype "passive"))
      (node (ref "C27") (pin "1") (pinfunction "1_1") (pintype "passive"))
      (node (ref "D1") (pin "1") (pinfunction "C_1") (pintype "passive"))
      (node (ref "D5") (pin "2") (pinfunction "A_2") (pintype "passive"))
      (node (ref "D6") (pin "2") (pinfunction "A_2") (pintype "bidirectional"))
      (node (ref "Q2") (pin "2") (pinfunction "D_2") (pintype "bidirectional"))
      (node (ref "R4") (pin "2") (pinfunction "2_2") (pintype "passive"))
      (node (ref "U3") (pin "9") (pinfunction "VCC_9") (pintype "bidirectional"))
    )
    (net (code "70") (name "unconnected-(J3-Pad01)") (class "Default")
      (node (ref "J3") (pin "01") (pinfunction "01_01") (pintype "passive"))
    )
    (net (code "71") (name "unconnected-(J3-Pad02)") (class "Default")
      (node (ref "J3") (pin "02") (pinfunction "02_02") (pintype "passive"))
    )
    (net (code "72") (name "unconnected-(J3-Pad08)") (class "Default")
      (node (ref "J3") (pin "08") (pinfunction "08_08") (pintype "passive"))
    )
    (net (code "73") (name "unconnected-(J3-Pad09)") (class "Default")
      (node (ref "J3") (pin "09") (pinfunction "09_09") (pintype "passive"))
    )
    (net (code "74") (name "unconnected-(J3-Pad10)") (class "Default")
      (node (ref "J3") (pin "10") (pinfunction "10_10") (pintype "passive"))
    )
    (net (code "75") (name "unconnected-(J3-Pad11)") (class "Default")
      (node (ref "J3") (pin "11") (pinfunction "11_11") (pintype "passive"))
    )
    (net (code "76") (name "unconnected-(J3-Pad13)") (class "Default")
      (node (ref "J3") (pin "13") (pinfunction "13_13") (pintype "passive"))
    )
    (net (code "77") (name "unconnected-(J3-Pad14)") (class "Default")
      (node (ref "J3") (pin "14") (pinfunction "14_14") (pintype "passive"))
    )
    (net (code "78") (name "unconnected-(J6-PadMP1)") (class "Default")
      (node (ref "J6") (pin "MP1") (pinfunction "MP1_MP1") (pintype "bidirectional"))
    )
    (net (code "79") (name "unconnected-(J6-PadMP2)") (class "Default")
      (node (ref "J6") (pin "MP2") (pinfunction "MP2_MP2") (pintype "bidirectional"))
    )
    (net (code "80") (name "unconnected-(U1-NIC_1-Pad4)") (class "Default")
      (node (ref "U1") (pin "4") (pinfunction "NIC_1_4") (pintype "bidirectional"))
    )
    (net (code "81") (name "unconnected-(U1-NIC_2-Pad6)") (class "Default")
      (node (ref "U1") (pin "6") (pinfunction "NIC_2_6") (pintype "bidirectional"))
    )
    (net (code "82") (name "unconnected-(U1-NIC_3-Pad7)") (class "Default")
      (node (ref "U1") (pin "7") (pinfunction "NIC_3_7") (pintype "bidirectional"))
    )
    (net (code "83") (name "unconnected-(U1-NIC_4-Pad8)") (class "Default")
      (node (ref "U1") (pin "8") (pinfunction "NIC_4_8") (pintype "bidirectional"))
    )
    (net (code "84") (name "unconnected-(U1-NIC_5-Pad13)") (class "Default")
      (node (ref "U1") (pin "13") (pinfunction "NIC_5_13") (pintype "bidirectional"))
    )
    (net (code "85") (name "unconnected-(U1-NIC_6-Pad14)") (class "Default")
      (node (ref "U1") (pin "14") (pinfunction "NIC_6_14") (pintype "bidirectional"))
    )
    (net (code "86") (name "unconnected-(U1-NIC_7-Pad15)") (class "Default")
      (node (ref "U1") (pin "15") (pinfunction "NIC_7_15") (pintype "bidirectional"))
    )
    (net (code "87") (name "unconnected-(U1-NIC_8-Pad16)") (class "Default")
      (node (ref "U1") (pin "16") (pinfunction "NIC_8_16") (pintype "bidirectional"))
    )
    (net (code "88") (name "unconnected-(U1-THERMAL_PAD-Pad17)") (class "Default")
      (node (ref "U1") (pin "17") (pinfunction "THERMAL_PAD_17") (pintype "bidirectional"))
    )
    (net (code "89") (name "unconnected-(U2-RFO_LP-Pad22)") (class "Default")
      (node (ref "U2") (pin "22") (pinfunction "RFO_LP_22") (pintype "bidirectional"))
    )
    (net (code "90") (name "unconnected-(U4-D1{slash}D2_1-Pad2)") (class "Default")
      (node (ref "U4") (pin "2") (pinfunction "D1/D2_1_2") (pintype "bidirectional"))
    )
    (net (code "91") (name "unconnected-(U4-D1{slash}D2_2-Pad5)") (class "Default")
      (node (ref "U4") (pin "5") (pinfunction "D1/D2_2_5") (pintype "bidirectional"))
    )
    (net (code "92") (name "unconnected-(U6-TD-Pad4)") (class "Default")
      (node (ref "U6") (pin "4") (pinfunction "TD_4") (pintype "bidirectional"))
    )
  )
)
